# EXIST_Transformer_PCB.net
KiCad netlist of a schematic drawn in EAGLE
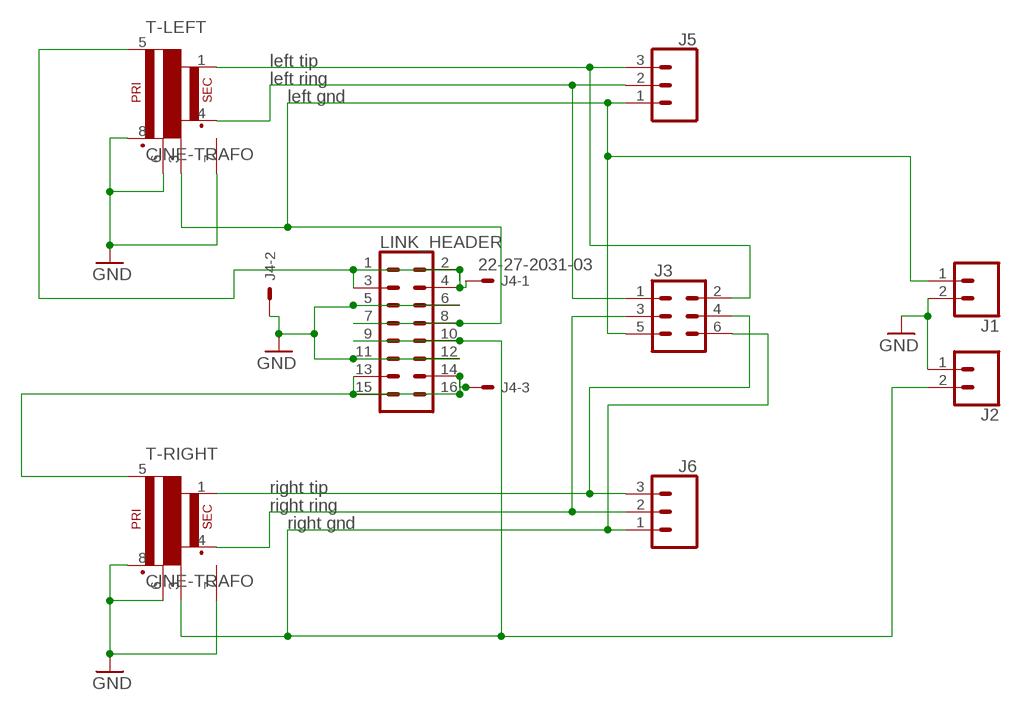
[diagram p0: schematic, sheet 1]

(export (version "E")
  (design (tool "Eeschema 10.0.6"))
  (components
    (comp (ref "J1")
      (value "CONN_02")
      (footprint "eagle-import:1X02")
      (libsource (lib "eagle-import") (part "CONN_02"))
    )
    (comp (ref "J2")
      (value "CONN_02")
      (footprint "eagle-import:1X02")
      (libsource (lib "eagle-import") (part "CONN_02"))
    )
    (comp (ref "J3")
      (value "CONN_03X22X3_SILK_MALE_PTH")
      (footprint "eagle-import:2X3")
      (libsource (lib "eagle-import") (part "CONN_03X22X3_SILK_MALE_PTH"))
    )
    (comp (ref "J4")
      (value "22-27-2031-03")
      (footprint "eagle-import:6410-03")
      (fields (field (name "MF") "MOLEX"))
      (libsource (lib "eagle-import") (part "22-?-0327-2031"))
    )
    (comp (ref "J5")
      (value "CONN_03LONGPADS")
      (footprint "eagle-import:1X03_LONGPADS")
      (libsource (lib "eagle-import") (part "CONN_03LONGPADS"))
    )
    (comp (ref "J6")
      (value "CONN_03LONGPADS")
      (footprint "eagle-import:1X03_LONGPADS")
      (libsource (lib "eagle-import") (part "CONN_03LONGPADS"))
    )
    (comp (ref "LINK_HEADER")
      (value "CONN_08X2")
      (footprint "eagle-import:2X8")
      (libsource (lib "eagle-import") (part "CONN_08X2"))
    )
    (comp (ref "T-LEFT")
      (value "CINE-TRAFO")
      (footprint "eagle-import:CIRC-TRAFO")
      (libsource (lib "eagle-import") (part "CINE-TRAFO"))
    )
    (comp (ref "T-RIGHT")
      (value "CINE-TRAFO")
      (footprint "eagle-import:CIRC-TRAFO")
      (libsource (lib "eagle-import") (part "CINE-TRAFO"))
    )
  )
  (nets
    (net (code "1") (name "GND") (class "Default")
      (node (ref "J1") (pin "2") (pinfunction "2_2") (pintype "passive"))
      (node (ref "J2") (pin "1") (pinfunction "1_1") (pintype "passive"))
      (node (ref "J4") (pin "2") (pinfunction "S_2") (pintype "passive"))
      (node (ref "LINK_HEADER") (pin "11") (pinfunction "11_11") (pintype "passive"))
      (node (ref "LINK_HEADER") (pin "12") (pinfunction "12_12") (pintype "passive"))
      (node (ref "LINK_HEADER") (pin "5") (pinfunction "5_5") (pintype "passive"))
      (node (ref "LINK_HEADER") (pin "6") (pinfunction "6_6") (pintype "passive"))
      (node (ref "T-LEFT") (pin "6") (pinfunction "C1_6") (pintype "passive"))
      (node (ref "T-LEFT") (pin "7") (pinfunction "CASE_7") (pintype "passive"))
      (node (ref "T-LEFT") (pin "8") (pinfunction "P2_8") (pintype "passive"))
      (node (ref "T-RIGHT") (pin "6") (pinfunction "C1_6") (pintype "passive"))
      (node (ref "T-RIGHT") (pin "7") (pinfunction "CASE_7") (pintype "passive"))
      (node (ref "T-RIGHT") (pin "8") (pinfunction "P2_8") (pintype "passive"))
    )
    (net (code "2") (name "Net-(J4A-S)") (class "Default")
      (node (ref "J4") (pin "1") (pinfunction "S_1") (pintype "passive"))
      (node (ref "LINK_HEADER") (pin "1") (pinfunction "1_1") (pintype "passive"))
      (node (ref "LINK_HEADER") (pin "2") (pinfunction "2_2") (pintype "passive"))
      (node (ref "LINK_HEADER") (pin "3") (pinfunction "3_3") (pintype "passive"))
      (node (ref "LINK_HEADER") (pin "4") (pinfunction "4_4") (pintype "passive"))
      (node (ref "T-LEFT") (pin "5") (pinfunction "P1_5") (pintype "passive"))
    )
    (net (code "3") (name "Net-(J4C-S)") (class "Default")
      (node (ref "J4") (pin "3") (pinfunction "S_3") (pintype "passive"))
      (node (ref "LINK_HEADER") (pin "13") (pinfunction "13_13") (pintype "passive"))
      (node (ref "LINK_HEADER") (pin "14") (pinfunction "14_14") (pintype "passive"))
      (node (ref "LINK_HEADER") (pin "15") (pinfunction "15_15") (pintype "passive"))
      (node (ref "LINK_HEADER") (pin "16") (pinfunction "16_16") (pintype "passive"))
      (node (ref "T-RIGHT") (pin "5") (pinfunction "P1_5") (pintype "passive"))
    )
    (net (code "4") (name "Net-(T-LEFT-C2)") (class "Default")
      (node (ref "J1") (pin "1") (pinfunction "1_1") (pintype "passive"))
      (node (ref "J3") (pin "5") (pinfunction "5_5") (pintype "bidirectional"))
      (node (ref "J5") (pin "1") (pinfunction "1_1") (pintype "passive"))
      (node (ref "LINK_HEADER") (pin "7") (pinfunction "7_7") (pintype "passive"))
      (node (ref "LINK_HEADER") (pin "8") (pinfunction "8_8") (pintype "passive"))
      (node (ref "T-LEFT") (pin "3") (pinfunction "C2_3") (pintype "passive"))
    )
    (net (code "5") (name "Net-(T-LEFT-S1)") (class "Default")
      (node (ref "J3") (pin "2") (pinfunction "2_2") (pintype "bidirectional"))
      (node (ref "J5") (pin "3") (pinfunction "3_3") (pintype "passive"))
      (node (ref "T-LEFT") (pin "1") (pinfunction "S1_1") (pintype "passive"))
    )
    (net (code "6") (name "Net-(T-LEFT-S2)") (class "Default")
      (node (ref "J3") (pin "1") (pinfunction "1_1") (pintype "bidirectional"))
      (node (ref "J5") (pin "2") (pinfunction "2_2") (pintype "passive"))
      (node (ref "T-LEFT") (pin "4") (pinfunction "S2_4") (pintype "passive"))
    )
    (net (code "7") (name "Net-(T-RIGHT-C2)") (class "Default")
      (node (ref "J2") (pin "2") (pinfunction "2_2") (pintype "passive"))
      (node (ref "J3") (pin "6") (pinfunction "6_6") (pintype "bidirectional"))
      (node (ref "J6") (pin "1") (pinfunction "1_1") (pintype "passive"))
      (node (ref "LINK_HEADER") (pin "10") (pinfunction "10_10") (pintype "passive"))
      (node (ref "LINK_HEADER") (pin "9") (pinfunction "9_9") (pintype "passive"))
      (node (ref "T-RIGHT") (pin "3") (pinfunction "C2_3") (pintype "passive"))
    )
    (net (code "8") (name "Net-(T-RIGHT-S1)") (class "Default")
      (node (ref "J3") (pin "4") (pinfunction "4_4") (pintype "bidirectional"))
      (node (ref "J6") (pin "3") (pinfunction "3_3") (pintype "passive"))
      (node (ref "T-RIGHT") (pin "1") (pinfunction "S1_1") (pintype "passive"))
    )
    (net (code "9") (name "Net-(T-RIGHT-S2)") (class "Default")
      (node (ref "J3") (pin "3") (pinfunction "3_3") (pintype "bidirectional"))
      (node (ref "J6") (pin "2") (pinfunction "2_2") (pintype "passive"))
      (node (ref "T-RIGHT") (pin "4") (pinfunction "S2_4") (pintype "passive"))
    )
  )
)
